# WSPRShield.net
KiCad netlist of a schematic drawn in Altium Designer
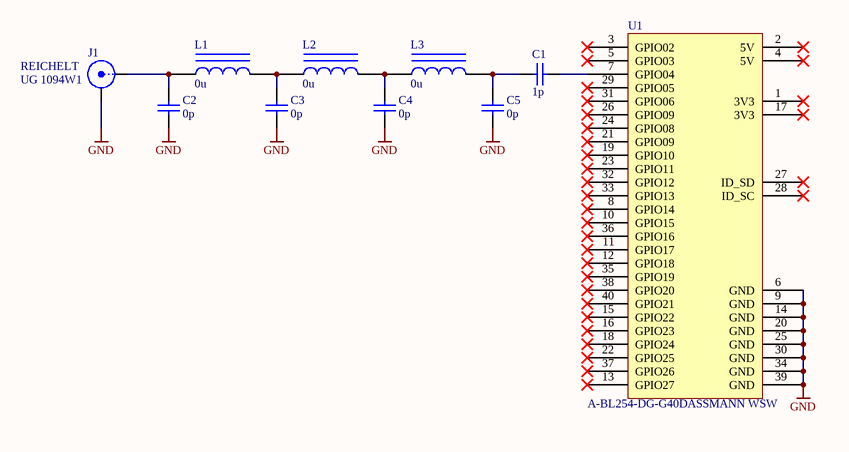
[diagram p0: WSPRShield.SchDoc]

(export (version "E")
  (design (tool "Eeschema 10.0.6"))
  (components
    (comp (ref "C1")
      (value "1p")
      (footprint "CER-CO-5MM")
      (fields
        (field (name "VOLTAGE") "100")
        (field (name "MANUFACTURER") "Miscellaneous")
        (field (name "Comment") "Capacitor")
      )
      (libsource (lib "ROLAND-LIB") (part "Capacitor"))
    )
    (comp (ref "C2")
      (value "0p")
      (footprint "CER-CO-5MM")
      (fields
        (field (name "VOLTAGE") "100")
        (field (name "MANUFACTURER") "Miscellaneous")
        (field (name "Comment") "Capacitor")
      )
      (libsource (lib "ROLAND-LIB") (part "Capacitor"))
    )
    (comp (ref "C3")
      (value "0p")
      (footprint "CER-CO-5MM")
      (fields
        (field (name "VOLTAGE") "100")
        (field (name "MANUFACTURER") "Miscellaneous")
        (field (name "Comment") "Capacitor")
      )
      (libsource (lib "ROLAND-LIB") (part "Capacitor"))
    )
    (comp (ref "C4")
      (value "0p")
      (footprint "CER-CO-5MM")
      (fields
        (field (name "VOLTAGE") "100")
        (field (name "MANUFACTURER") "Miscellaneous")
        (field (name "Comment") "Capacitor")
      )
      (libsource (lib "ROLAND-LIB") (part "Capacitor"))
    )
    (comp (ref "C5")
      (value "0p")
      (footprint "CER-CO-5MM")
      (fields
        (field (name "VOLTAGE") "100")
        (field (name "MANUFACTURER") "Miscellaneous")
        (field (name "Comment") "Capacitor")
      )
      (libsource (lib "ROLAND-LIB") (part "Capacitor"))
    )
    (comp (ref "J1")
      (value "COAX")
      (footprint "REICHELT_UG1094W1")
      (fields (field (name "MANUFACTURER") "REICHELT") (field (name "TYPE") "UG 1094W1"))
      (libsource (lib "ROLAND-LIB") (part "COAX"))
    )
    (comp (ref "L1")
      (value "0u")
      (footprint "T37-6")
      (fields (field (name "Comment") "Inductor (IronCore)"))
      (libsource (lib "ROLAND-LIB") (part "Inductor (IronCore)"))
    )
    (comp (ref "L2")
      (value "0u")
      (footprint "T37-6")
      (fields (field (name "Comment") "Inductor (IronCore)"))
      (libsource (lib "ROLAND-LIB") (part "Inductor (IronCore)"))
    )
    (comp (ref "L3")
      (value "0u")
      (footprint "T37-6")
      (fields (field (name "Comment") "Inductor (IronCore)"))
      (libsource (lib "ROLAND-LIB") (part "Inductor (IronCore)"))
    )
    (comp (ref "U1")
      (value "RaspberryPiB")
      (footprint "RASPI_BPHAT")
      (fields (field (name "TYPE") "A-BL254-DG-G40DASSMANN WSW") (field (name "MANUFACTURER") "ASSMANN"))
      (libsource (lib "ROLAND-LIB") (part "RaspberryPiB"))
    )
  )
  (nets
    (net (code "1") (name "GND") (class "Default")
      (node (ref "C2") (pin "1") (pinfunction "1_1") (pintype "passive"))
      (node (ref "C3") (pin "1") (pinfunction "1_1") (pintype "passive"))
      (node (ref "C4") (pin "1") (pinfunction "1_1") (pintype "passive"))
      (node (ref "C5") (pin "1") (pinfunction "1_1") (pintype "passive"))
      (node (ref "J1") (pin "2") (pinfunction "Y_2") (pintype "passive"))
      (node (ref "U1") (pin "14") (pinfunction "GND_14") (pintype "passive"))
      (node (ref "U1") (pin "20") (pinfunction "GND_20") (pintype "passive"))
      (node (ref "U1") (pin "25") (pinfunction "GND_25") (pintype "passive"))
      (node (ref "U1") (pin "30") (pinfunction "GND_30") (pintype "passive"))
      (node (ref "U1") (pin "34") (pinfunction "GND_34") (pintype "passive"))
      (node (ref "U1") (pin "39") (pinfunction "GND_39") (pintype "passive"))
      (node (ref "U1") (pin "6") (pinfunction "GND_6") (pintype "passive"))
      (node (ref "U1") (pin "9") (pinfunction "GND_9") (pintype "passive"))
    )
    (net (code "2") (name "Net-(C1-Pad2)") (class "Default")
      (node (ref "C1") (pin "2") (pinfunction "2_2") (pintype "passive"))
      (node (ref "C5") (pin "2") (pinfunction "2_2") (pintype "passive"))
      (node (ref "L3") (pin "2") (pinfunction "2_2") (pintype "passive"))
    )
    (net (code "3") (name "Net-(C3-Pad2)") (class "Default")
      (node (ref "C3") (pin "2") (pinfunction "2_2") (pintype "passive"))
      (node (ref "L1") (pin "2") (pinfunction "2_2") (pintype "passive"))
      (node (ref "L2") (pin "1") (pinfunction "1_1") (pintype "passive"))
    )
    (net (code "4") (name "Net-(C4-Pad2)") (class "Default")
      (node (ref "C4") (pin "2") (pinfunction "2_2") (pintype "passive"))
      (node (ref "L2") (pin "2") (pinfunction "2_2") (pintype "passive"))
      (node (ref "L3") (pin "1") (pinfunction "1_1") (pintype "passive"))
    )
    (net (code "5") (name "Net-(J1-X)") (class "Default")
      (node (ref "C2") (pin "2") (pinfunction "2_2") (pintype "passive"))
      (node (ref "J1") (pin "1") (pinfunction "X_1") (pintype "passive"))
      (node (ref "L1") (pin "1") (pinfunction "1_1") (pintype "passive"))
    )
    (net (code "6") (name "Net-(U1-GPIO04)") (class "Default")
      (node (ref "C1") (pin "1") (pinfunction "1_1") (pintype "passive"))
      (node (ref "U1") (pin "7") (pinfunction "GPIO04_7") (pintype "passive"))
    )
    (net (code "7") (name "unconnected-(U1-3V3-Pad1)") (class "Default")
      (node (ref "U1") (pin "1") (pinfunction "3V3_1") (pintype "passive+no_connect"))
    )
    (net (code "8") (name "unconnected-(U1-3V3-Pad17)") (class "Default")
      (node (ref "U1") (pin "17") (pinfunction "3V3_17") (pintype "passive+no_connect"))
    )
    (net (code "9") (name "unconnected-(U1-5V-Pad2)") (class "Default")
      (node (ref "U1") (pin "2") (pinfunction "5V_2") (pintype "passive+no_connect"))
    )
    (net (code "10") (name "unconnected-(U1-5V-Pad4)") (class "Default")
      (node (ref "U1") (pin "4") (pinfunction "5V_4") (pintype "passive+no_connect"))
    )
    (net (code "11") (name "unconnected-(U1-GPIO02-Pad3)") (class "Default")
      (node (ref "U1") (pin "3") (pinfunction "GPIO02_3") (pintype "passive+no_connect"))
    )
    (net (code "12") (name "unconnected-(U1-GPIO03-Pad5)") (class "Default")
      (node (ref "U1") (pin "5") (pinfunction "GPIO03_5") (pintype "passive+no_connect"))
    )
    (net (code "13") (name "unconnected-(U1-GPIO05-Pad29)") (class "Default")
      (node (ref "U1") (pin "29") (pinfunction "GPIO05_29") (pintype "passive+no_connect"))
    )
    (net (code "14") (name "unconnected-(U1-GPIO06-Pad31)") (class "Default")
      (node (ref "U1") (pin "31") (pinfunction "GPIO06_31") (pintype "passive+no_connect"))
    )
    (net (code "15") (name "unconnected-(U1-GPIO08-Pad24)") (class "Default")
      (node (ref "U1") (pin "24") (pinfunction "GPIO08_24") (pintype "passive+no_connect"))
    )
    (net (code "16") (name "unconnected-(U1-GPIO09-Pad21)") (class "Default")
      (node (ref "U1") (pin "21") (pinfunction "GPIO09_21") (pintype "passive+no_connect"))
    )
    (net (code "17") (name "unconnected-(U1-GPIO09-Pad26)") (class "Default")
      (node (ref "U1") (pin "26") (pinfunction "GPIO09_26") (pintype "passive+no_connect"))
    )
    (net (code "18") (name "unconnected-(U1-GPIO10-Pad19)") (class "Default")
      (node (ref "U1") (pin "19") (pinfunction "GPIO10_19") (pintype "passive+no_connect"))
    )
    (net (code "19") (name "unconnected-(U1-GPIO11-Pad23)") (class "Default")
      (node (ref "U1") (pin "23") (pinfunction "GPIO11_23") (pintype "passive+no_connect"))
    )
    (net (code "20") (name "unconnected-(U1-GPIO12-Pad32)") (class "Default")
      (node (ref "U1") (pin "32") (pinfunction "GPIO12_32") (pintype "passive+no_connect"))
    )
    (net (code "21") (name "unconnected-(U1-GPIO13-Pad33)") (class "Default")
      (node (ref "U1") (pin "33") (pinfunction "GPIO13_33") (pintype "passive+no_connect"))
    )
    (net (code "22") (name "unconnected-(U1-GPIO14-Pad8)") (class "Default")
      (node (ref "U1") (pin "8") (pinfunction "GPIO14_8") (pintype "passive+no_connect"))
    )
    (net (code "23") (name "unconnected-(U1-GPIO15-Pad10)") (class "Default")
      (node (ref "U1") (pin "10") (pinfunction "GPIO15_10") (pintype "passive+no_connect"))
    )
    (net (code "24") (name "unconnected-(U1-GPIO16-Pad36)") (class "Default")
      (node (ref "U1") (pin "36") (pinfunction "GPIO16_36") (pintype "passive+no_connect"))
    )
    (net (code "25") (name "unconnected-(U1-GPIO17-Pad11)") (class "Default")
      (node (ref "U1") (pin "11") (pinfunction "GPIO17_11") (pintype "passive+no_connect"))
    )
    (net (code "26") (name "unconnected-(U1-GPIO18-Pad12)") (class "Default")
      (node (ref "U1") (pin "12") (pinfunction "GPIO18_12") (pintype "passive+no_connect"))
    )
    (net (code "27") (name "unconnected-(U1-GPIO19-Pad35)") (class "Default")
      (node (ref "U1") (pin "35") (pinfunction "GPIO19_35") (pintype "passive+no_connect"))
    )
    (net (code "28") (name "unconnected-(U1-GPIO20-Pad38)") (class "Default")
      (node (ref "U1") (pin "38") (pinfunction "GPIO20_38") (pintype "passive+no_connect"))
    )
    (net (code "29") (name "unconnected-(U1-GPIO21-Pad40)") (class "Default")
      (node (ref "U1") (pin "40") (pinfunction "GPIO21_40") (pintype "passive+no_connect"))
    )
    (net (code "30") (name "unconnected-(U1-GPIO22-Pad15)") (class "Default")
      (node (ref "U1") (pin "15") (pinfunction "GPIO22_15") (pintype "passive+no_connect"))
    )
    (net (code "31") (name "unconnected-(U1-GPIO23-Pad16)") (class "Default")
      (node (ref "U1") (pin "16") (pinfunction "GPIO23_16") (pintype "passive+no_connect"))
    )
    (net (code "32") (name "unconnected-(U1-GPIO24-Pad18)") (class "Default")
      (node (ref "U1") (pin "18") (pinfunction "GPIO24_18") (pintype "passive+no_connect"))
    )
    (net (code "33") (name "unconnected-(U1-GPIO25-Pad22)") (class "Default")
      (node (ref "U1") (pin "22") (pinfunction "GPIO25_22") (pintype "passive+no_connect"))
    )
    (net (code "34") (name "unconnected-(U1-GPIO26-Pad37)") (class "Default")
      (node (ref "U1") (pin "37") (pinfunction "GPIO26_37") (pintype "passive+no_connect"))
    )
    (net (code "35") (name "unconnected-(U1-GPIO27-Pad13)") (class "Default")
      (node (ref "U1") (pin "13") (pinfunction "GPIO27_13") (pintype "passive+no_connect"))
    )
    (net (code "36") (name "unconnected-(U1-ID_SC-Pad28)") (class "Default")
      (node (ref "U1") (pin "28") (pinfunction "ID_SC_28") (pintype "passive+no_connect"))
    )
    (net (code "37") (name "unconnected-(U1-ID_SD-Pad27)") (class "Default")
      (node (ref "U1") (pin "27") (pinfunction "ID_SD_27") (pintype "passive+no_connect"))
    )
  )
)
